# CarrotDriver.net
KiCad netlist of a schematic drawn in Altium Designer
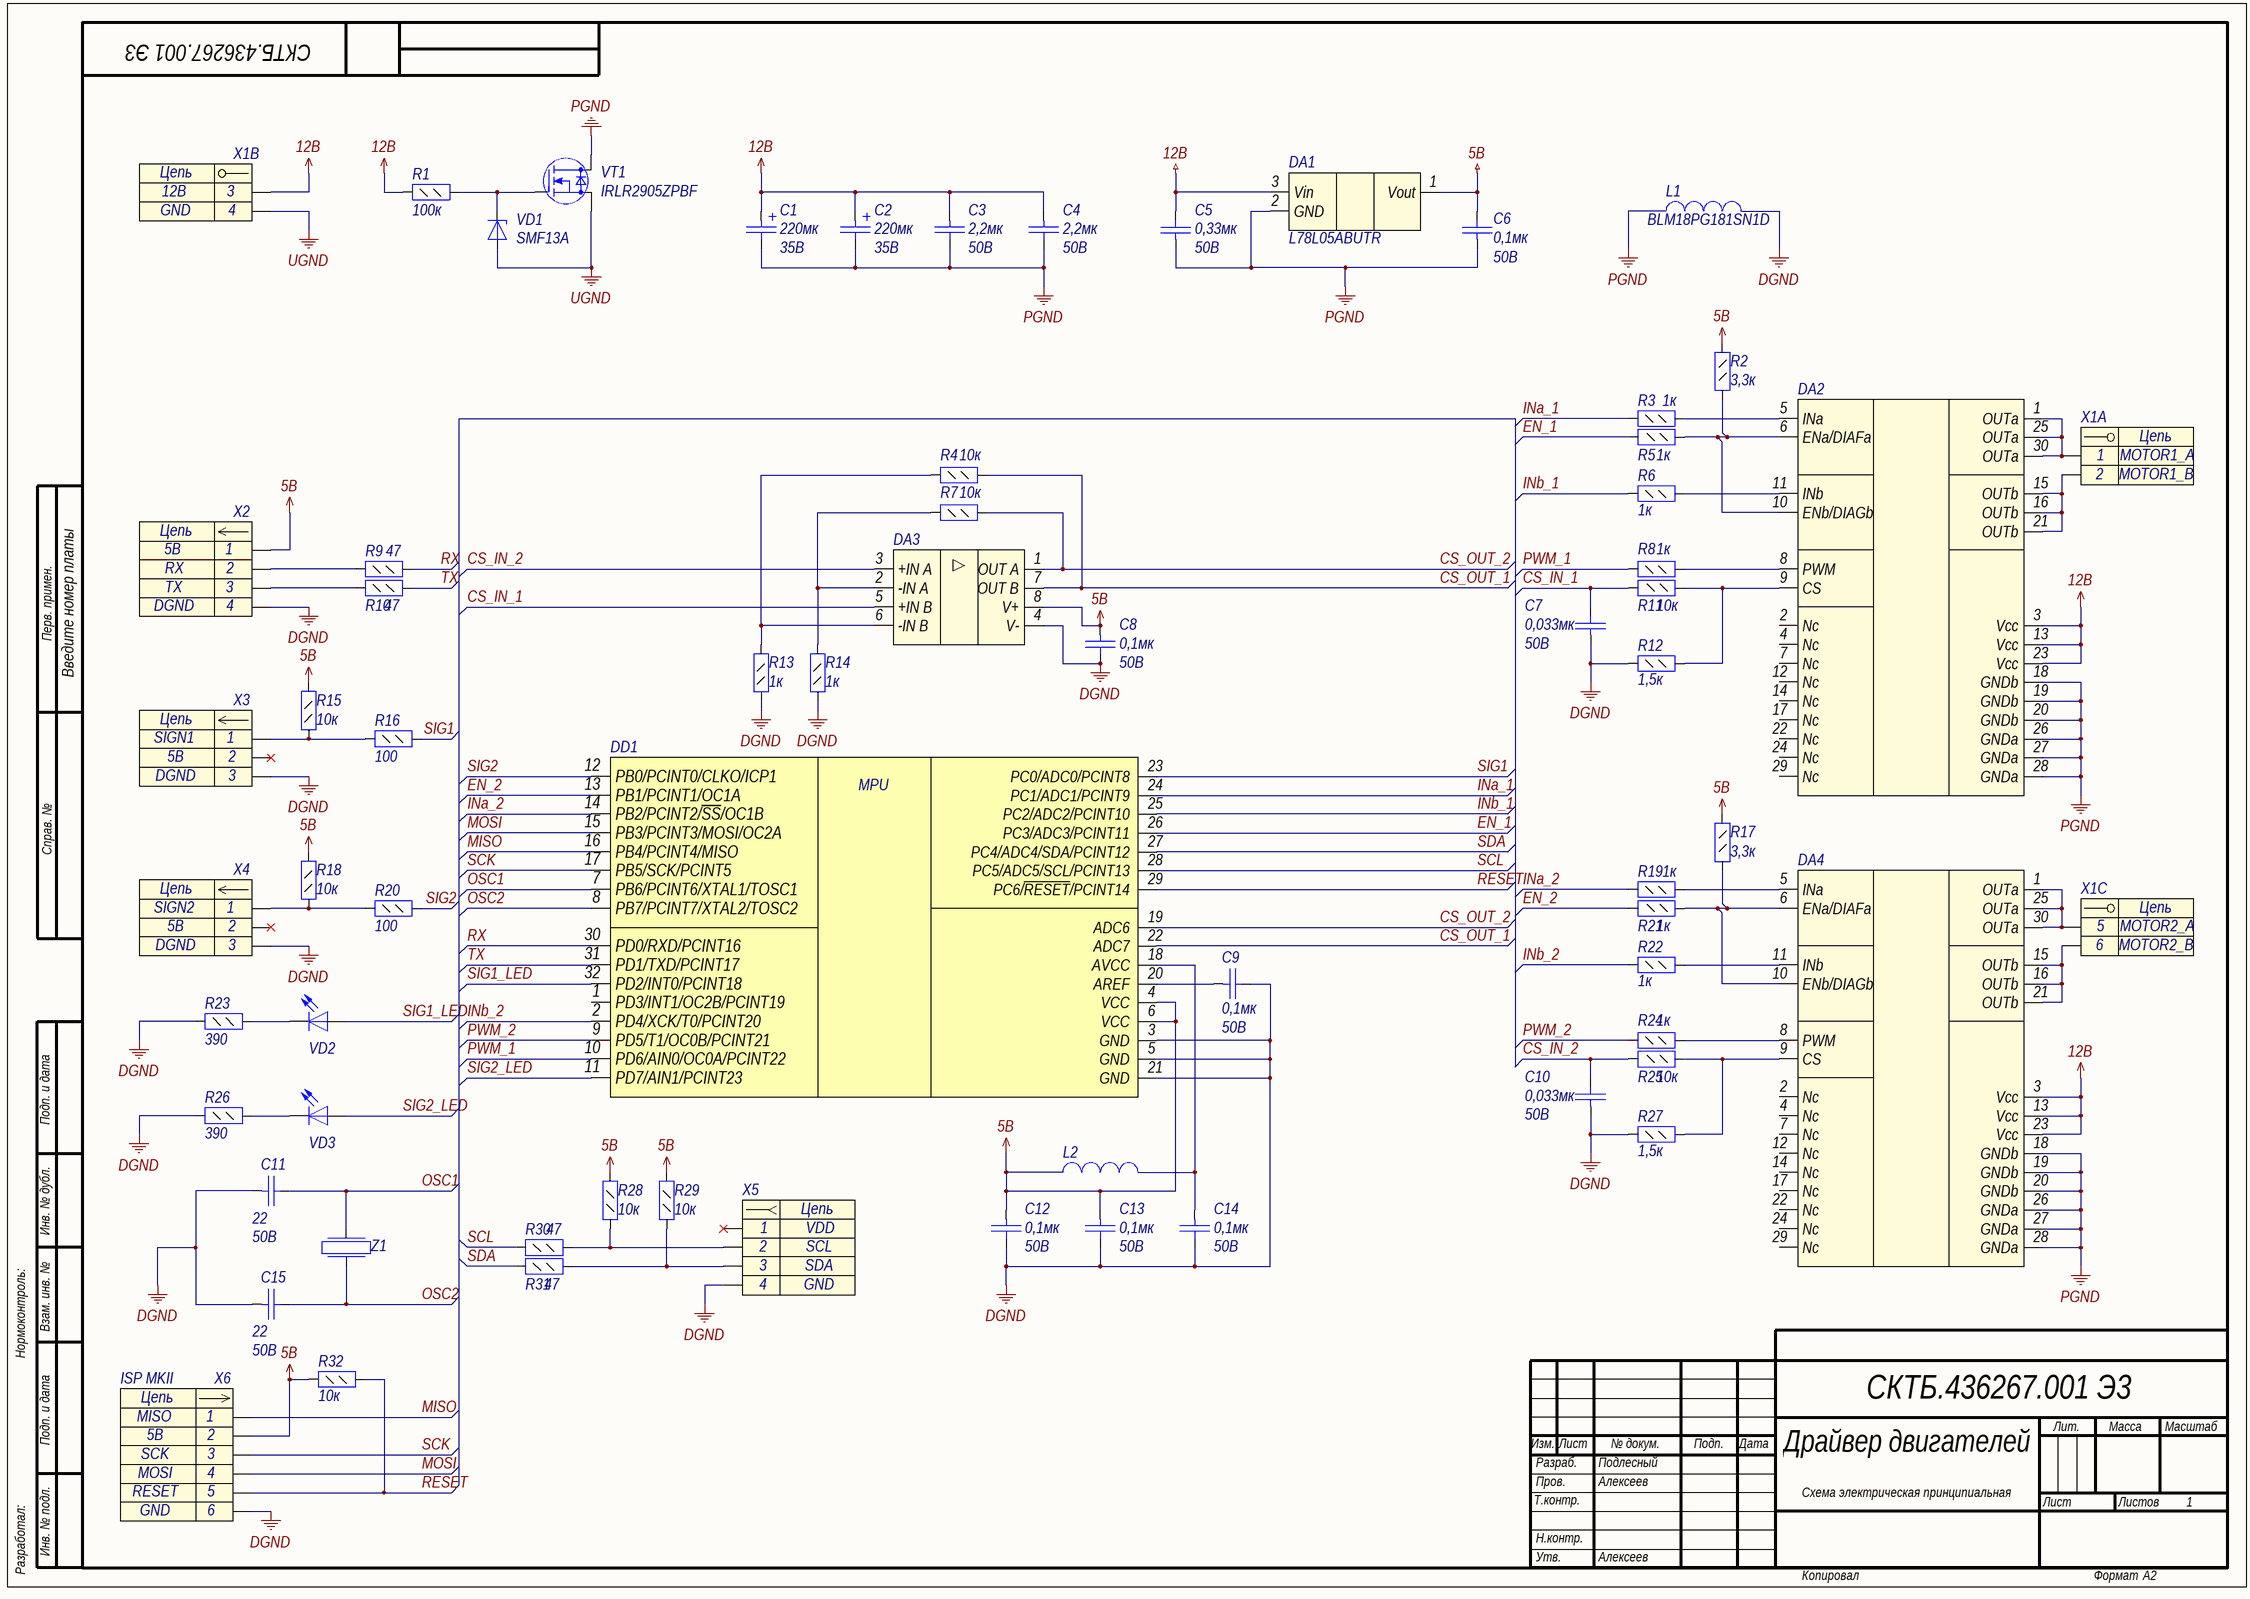
[diagram p0: CarrotDriver.SchDoc]

(export (version "E")
  (design (tool "Eeschema 10.0.6"))
  (components
    (comp (ref "C1")
      (value "220мк")
      (footprint "k50-35(8x11.5)_MIRROR")
      (description "Конденсатор полярный")
      (fields
        (field (name "VOLTAGE") "35В")
        (field (name "PART NUMBER") "TKR221M1VF11")
        (field (name "Comment") "Capacitor_pol")
      )
      (libsource (lib "MOP44") (part "Capacitor_pol"))
    )
    (comp (ref "C2")
      (value "220мк")
      (footprint "k50-35(8x11.5)_MIRROR")
      (description "Конденсатор полярный")
      (fields
        (field (name "VOLTAGE") "35В")
        (field (name "PART NUMBER") "TKR221M1VF11")
        (field (name "Comment") "Capacitor_pol")
      )
      (libsource (lib "MOP44") (part "Capacitor_pol"))
    )
    (comp (ref "C3")
      (value "2,2мк")
      (footprint "C1206")
      (description "Конденсатор")
      (fields
        (field (name "VOLTAGE") "50В")
        (field (name "PART NUMBER") "GRM31CR71H225KA88**L")
        (field (name "Comment") "Capacitor")
      )
      (libsource (lib "MOP44") (part "Capacitor"))
    )
    (comp (ref "C4")
      (value "2,2мк")
      (footprint "C1206")
      (description "Конденсатор")
      (fields
        (field (name "VOLTAGE") "50В")
        (field (name "PART NUMBER") "GRM31CR71H225KA88**L")
        (field (name "Comment") "Capacitor")
      )
      (libsource (lib "MOP44") (part "Capacitor"))
    )
    (comp (ref "C5")
      (value "0,33мк")
      (footprint "C1206")
      (description "Конденсатор")
      (fields
        (field (name "VOLTAGE") "50В")
        (field (name "PART NUMBER") "GRM319R71H334K")
        (field (name "Comment") "Capacitor")
      )
      (libsource (lib "MOP44") (part "Capacitor"))
    )
    (comp (ref "C6")
      (value "0,1мк")
      (footprint "C0805")
      (description "Конденсатор")
      (fields
        (field (name "VOLTAGE") "50В")
        (field (name "PART NUMBER") "GRM21BR71H104KA01L ")
        (field (name "Comment") "Capacitor")
      )
      (libsource (lib "MOP44") (part "Capacitor"))
    )
    (comp (ref "C7")
      (value "0,033мк")
      (footprint "C1206")
      (description "Конденсатор")
      (fields
        (field (name "VOLTAGE") "50В")
        (field (name "PART NUMBER") "GRM3195C1H333J")
        (field (name "Comment") "Capacitor")
      )
      (libsource (lib "MOP44") (part "Capacitor"))
    )
    (comp (ref "C8")
      (value "0,1мк")
      (footprint "C0805")
      (description "Конденсатор")
      (fields
        (field (name "VOLTAGE") "50В")
        (field (name "PART NUMBER") "GRM216R71H221K")
        (field (name "Comment") "Capacitor")
      )
      (libsource (lib "MOP44") (part "Capacitor"))
    )
    (comp (ref "C9")
      (value "0,1мк")
      (footprint "C0805")
      (description "Конденсатор")
      (fields
        (field (name "VOLTAGE") "50В")
        (field (name "PART NUMBER") "GRM216R71H221K")
        (field (name "Comment") "Capacitor")
      )
      (libsource (lib "MOP44") (part "Capacitor"))
    )
    (comp (ref "C10")
      (value "0,033мк")
      (footprint "C1206")
      (description "Конденсатор")
      (fields
        (field (name "VOLTAGE") "50В")
        (field (name "PART NUMBER") "GRM3195C1H333J")
        (field (name "Comment") "Capacitor")
      )
      (libsource (lib "MOP44") (part "Capacitor"))
    )
    (comp (ref "C11")
      (value "22")
      (footprint "C0805")
      (description "Конденсатор")
      (fields
        (field (name "VOLTAGE") "50В")
        (field (name "PART NUMBER") "GRM21A5C2E220JW01D")
        (field (name "Comment") "Capacitor")
      )
      (libsource (lib "MOP44") (part "Capacitor"))
    )
    (comp (ref "C12")
      (value "0,1мк")
      (footprint "C0805")
      (description "Конденсатор")
      (fields
        (field (name "VOLTAGE") "50В")
        (field (name "PART NUMBER") "GRM216R71H221K")
        (field (name "Comment") "Capacitor")
      )
      (libsource (lib "MOP44") (part "Capacitor"))
    )
    (comp (ref "C13")
      (value "0,1мк")
      (footprint "C0805")
      (description "Конденсатор")
      (fields
        (field (name "VOLTAGE") "50В")
        (field (name "PART NUMBER") "GRM216R71H221K")
        (field (name "Comment") "Capacitor")
      )
      (libsource (lib "MOP44") (part "Capacitor"))
    )
    (comp (ref "C14")
      (value "0,1мк")
      (footprint "C0805")
      (description "Конденсатор")
      (fields
        (field (name "VOLTAGE") "50В")
        (field (name "PART NUMBER") "GRM216R71H221K")
        (field (name "Comment") "Capacitor")
      )
      (libsource (lib "MOP44") (part "Capacitor"))
    )
    (comp (ref "C15")
      (value "22")
      (footprint "C0805")
      (description "Конденсатор")
      (fields
        (field (name "VOLTAGE") "50В")
        (field (name "PART NUMBER") "GRM21A5C2E220JW01D")
        (field (name "Comment") "Capacitor")
      )
      (libsource (lib "MOP44") (part "Capacitor"))
    )
    (comp (ref "DA1")
      (value "L78L05ABUTR")
      (footprint "SOT-89-3")
      (description "Cтабилизатор напряжения (+5В; 0.1А), 4%, (-40...+125C)")
      (fields (field (name "MANUFACTURER") "ST Microelectronics"))
      (libsource (lib "MOP44") (part "L78L05ABUTR"))
    )
    (comp (ref "DA2")
      (value "VNH2SP30-E")
      (footprint "MultiPowerSO-30")
      (description "Automotive fully integrated H-bridge motor driver")
      (libsource (lib "MOP44") (part "VNH2SP30-E"))
    )
    (comp (ref "DA3")
      (value "LMV358IDR")
      (footprint "SO8")
      (description "LOW-VOLTAGE RAIL-TO-RAIL OUTPUT OPERATIONAL AMPLIFIERS")
      (libsource (lib "MOP44") (part "LMV358IDR"))
    )
    (comp (ref "DA4")
      (value "VNH2SP30-E")
      (footprint "MultiPowerSO-30")
      (description "Automotive fully integrated H-bridge motor driver")
      (libsource (lib "MOP44") (part "VNH2SP30-E"))
    )
    (comp (ref "DD1")
      (value "ATmega328P-AU")
      (footprint "TQFP-32")
      (description "Микроконтроллер 8-Бит, picoPower, AVR, 20МГц, 32КБ Flash")
      (libsource (lib "MOP44") (part "ATmega328P-AU"))
    )
    (comp (ref "L1")
      (value "Inductor")
      (footprint "L0603")
      (description "EMI Suppression Filter")
      (fields (field (name "PART NUMBER") "BLM18PG181SN1D"))
      (libsource (lib "MOP44") (part "Inductor"))
    )
    (comp (ref "L2")
      (value "Inductor")
      (footprint "L0603")
      (description "EMI Suppression Filter")
      (fields (field (name "PART NUMBER") "BLM18PG181SN1D"))
      (libsource (lib "MOP44") (part "Inductor"))
    )
    (comp (ref "R1")
      (value "100к")
      (footprint "R0805")
      (description "Резистор")
      (fields (field (name "PART NUMBER") "RC0805FR-07100KL") (field (name "POWER") "0,125Вт"))
      (libsource (lib "MOP44") (part "Resistor_0,125Вт"))
    )
    (comp (ref "R2")
      (value "3,3к")
      (footprint "R0805")
      (description "Резистор")
      (fields (field (name "PART NUMBER") "RC0805FR-0710KL") (field (name "POWER") "0,125Вт"))
      (libsource (lib "") (part "Resistor_0,125Вт_3"))
    )
    (comp (ref "R3")
      (value "1к")
      (footprint "R0805")
      (description "Резистор")
      (fields (field (name "PART NUMBER") "RC0805FR-0710KL") (field (name "POWER") "0,125Вт"))
      (libsource (lib "MOP44") (part "Resistor_0,125Вт"))
    )
    (comp (ref "R4")
      (value "10к")
      (footprint "R0805")
      (description "Резистор")
      (fields (field (name "PART NUMBER") "RC0805FR-0710KL") (field (name "POWER") "0,125Вт"))
      (libsource (lib "MOP44") (part "Resistor_0,125Вт"))
    )
    (comp (ref "R5")
      (value "1к")
      (footprint "R0805")
      (description "Резистор")
      (fields (field (name "PART NUMBER") "RC0805FR-0710KL") (field (name "POWER") "0,125Вт"))
      (libsource (lib "") (part "Resistor_0,125Вт_1"))
    )
    (comp (ref "R6")
      (value "1к")
      (footprint "R0805")
      (description "Резистор")
      (fields (field (name "PART NUMBER") "RC0805FR-0710KL") (field (name "POWER") "0,125Вт"))
      (libsource (lib "MOP44") (part "Resistor_0,125Вт"))
    )
    (comp (ref "R7")
      (value "10к")
      (footprint "R0805")
      (description "Резистор")
      (fields (field (name "PART NUMBER") "RC0805FR-0710KL") (field (name "POWER") "0,125Вт"))
      (libsource (lib "MOP44") (part "Resistor_0,125Вт"))
    )
    (comp (ref "R8")
      (value "1к")
      (footprint "R0805")
      (description "Резистор")
      (fields (field (name "PART NUMBER") "RC0805FR-0710KL") (field (name "POWER") "0,125Вт"))
      (libsource (lib "MOP44") (part "Resistor_0,125Вт"))
    )
    (comp (ref "R9")
      (value "47")
      (footprint "R0805")
      (description "Резистор")
      (fields (field (name "PART NUMBER") "RC0805FR-0747RL") (field (name "POWER") "0,125Вт"))
      (libsource (lib "MOP44") (part "Resistor_0,125Вт"))
    )
    (comp (ref "R10")
      (value "47")
      (footprint "R0805")
      (description "Резистор")
      (fields (field (name "PART NUMBER") "RC0805FR-0747RL") (field (name "POWER") "0,125Вт"))
      (libsource (lib "MOP44") (part "Resistor_0,125Вт"))
    )
    (comp (ref "R11")
      (value "10к")
      (footprint "R0805")
      (description "Резистор")
      (fields (field (name "PART NUMBER") "RC0805FR-0710KL") (field (name "POWER") "0,125Вт"))
      (libsource (lib "") (part "Resistor_0,125Вт_1"))
    )
    (comp (ref "R12")
      (value "1,5к")
      (footprint "R0805")
      (description "Резистор")
      (fields (field (name "PART NUMBER") "RC0805FR-0710KL") (field (name "POWER") "0,125Вт"))
      (libsource (lib "MOP44") (part "Resistor_0,125Вт"))
    )
    (comp (ref "R13")
      (value "1к")
      (footprint "R0805")
      (description "Резистор")
      (fields (field (name "PART NUMBER") "RC0805FR-071KL") (field (name "POWER") "0,125Вт"))
      (libsource (lib "") (part "Resistor_0,125Вт_2"))
    )
    (comp (ref "R14")
      (value "1к")
      (footprint "R0805")
      (description "Резистор")
      (fields (field (name "PART NUMBER") "RC0805FR-071KL") (field (name "POWER") "0,125Вт"))
      (libsource (lib "") (part "Resistor_0,125Вт_2"))
    )
    (comp (ref "R15")
      (value "10к")
      (footprint "R0805")
      (description "Резистор")
      (fields (field (name "PART NUMBER") "RC0805FR-0710KL") (field (name "POWER") "0,125Вт"))
      (libsource (lib "") (part "Resistor_0,125Вт_2"))
    )
    (comp (ref "R16")
      (value "100")
      (footprint "R0805")
      (description "Резистор")
      (fields (field (name "PART NUMBER") "RC0805FR-07100RL") (field (name "POWER") "0,125Вт"))
      (libsource (lib "MOP44") (part "Resistor_0,125Вт"))
    )
    (comp (ref "R17")
      (value "3,3к")
      (footprint "R0805")
      (description "Резистор")
      (fields (field (name "PART NUMBER") "RC0805FR-0710KL") (field (name "POWER") "0,125Вт"))
      (libsource (lib "") (part "Resistor_0,125Вт_3"))
    )
    (comp (ref "R18")
      (value "10к")
      (footprint "R0805")
      (description "Резистор")
      (fields (field (name "PART NUMBER") "RC0805FR-0710KL") (field (name "POWER") "0,125Вт"))
      (libsource (lib "") (part "Resistor_0,125Вт_2"))
    )
    (comp (ref "R19")
      (value "1к")
      (footprint "R0805")
      (description "Резистор")
      (fields (field (name "PART NUMBER") "RC0805FR-0710KL") (field (name "POWER") "0,125Вт"))
      (libsource (lib "MOP44") (part "Resistor_0,125Вт"))
    )
    (comp (ref "R20")
      (value "100")
      (footprint "R0805")
      (description "Резистор")
      (fields (field (name "PART NUMBER") "RC0805FR-07100RL") (field (name "POWER") "0,125Вт"))
      (libsource (lib "MOP44") (part "Resistor_0,125Вт"))
    )
    (comp (ref "R21")
      (value "1к")
      (footprint "R0805")
      (description "Резистор")
      (fields (field (name "PART NUMBER") "RC0805FR-0710KL") (field (name "POWER") "0,125Вт"))
      (libsource (lib "") (part "Resistor_0,125Вт_1"))
    )
    (comp (ref "R22")
      (value "1к")
      (footprint "R0805")
      (description "Резистор")
      (fields (field (name "PART NUMBER") "RC0805FR-0710KL") (field (name "POWER") "0,125Вт"))
      (libsource (lib "MOP44") (part "Resistor_0,125Вт"))
    )
    (comp (ref "R23")
      (value "390")
      (footprint "R0805")
      (description "Резистор")
      (fields (field (name "PART NUMBER") "RC0805FR-07390RL") (field (name "POWER") "0,125Вт"))
      (libsource (lib "MOP44") (part "Resistor_0,125Вт"))
    )
    (comp (ref "R24")
      (value "1к")
      (footprint "R0805")
      (description "Резистор")
      (fields (field (name "PART NUMBER") "RC0805FR-0710KL") (field (name "POWER") "0,125Вт"))
      (libsource (lib "MOP44") (part "Resistor_0,125Вт"))
    )
    (comp (ref "R25")
      (value "10к")
      (footprint "R0805")
      (description "Резистор")
      (fields (field (name "PART NUMBER") "RC0805FR-0710KL") (field (name "POWER") "0,125Вт"))
      (libsource (lib "") (part "Resistor_0,125Вт_1"))
    )
    (comp (ref "R26")
      (value "390")
      (footprint "R0805")
      (description "Резистор")
      (fields (field (name "PART NUMBER") "RC0805FR-07390RL") (field (name "POWER") "0,125Вт"))
      (libsource (lib "MOP44") (part "Resistor_0,125Вт"))
    )
    (comp (ref "R27")
      (value "1,5к")
      (footprint "R0805")
      (description "Резистор")
      (fields (field (name "PART NUMBER") "RC0805FR-0710KL") (field (name "POWER") "0,125Вт"))
      (libsource (lib "MOP44") (part "Resistor_0,125Вт"))
    )
    (comp (ref "R28")
      (value "10к")
      (footprint "R0805")
      (description "Резистор")
      (fields (field (name "PART NUMBER") "RC0805FR-0710KL") (field (name "POWER") "0,125Вт"))
      (libsource (lib "MOP44") (part "Resistor_0,125Вт"))
    )
    (comp (ref "R29")
      (value "10к")
      (footprint "R0805")
      (description "Резистор")
      (fields (field (name "PART NUMBER") "RC0805FR-0710KL") (field (name "POWER") "0,125Вт"))
      (libsource (lib "MOP44") (part "Resistor_0,125Вт"))
    )
    (comp (ref "R30")
      (value "47")
      (footprint "R0805")
      (description "Резистор")
      (fields (field (name "PART NUMBER") "RC0805FR-0747RL") (field (name "POWER") "0,125Вт"))
      (libsource (lib "MOP44") (part "Resistor_0,125Вт"))
    )
    (comp (ref "R31")
      (value "47")
      (footprint "R0805")
      (description "Резистор")
      (fields (field (name "PART NUMBER") "RC0805FR-0747RL") (field (name "POWER") "0,125Вт"))
      (libsource (lib "MOP44") (part "Resistor_0,125Вт"))
    )
    (comp (ref "R32")
      (value "10к")
      (footprint "R0805")
      (description "Резистор")
      (fields (field (name "PART NUMBER") "RC0805FR-0710KL") (field (name "POWER") "0,125Вт"))
      (libsource (lib "MOP44") (part "Resistor_0,125Вт"))
    )
    (comp (ref "VD1")
      (value "DiodeZener")
      (footprint "SOD-123")
      (description "Cтабилитрон (лавинный выпрямительный диод) односторонний")
      (fields (field (name "PART NUMBER") "SMF13A"))
      (libsource (lib "MOP44") (part "DiodeZener"))
    )
    (comp (ref "VD2")
      (value "LED")
      (footprint "L_0805")
      (description "Светодиод")
      (fields (field (name "PART NUMBER") "KP-2012EC"))
      (libsource (lib "MOP44") (part "LED"))
    )
    (comp (ref "VD3")
      (value "LED")
      (footprint "L_0805")
      (description "Светодиод")
      (fields (field (name "PART NUMBER") "KP-2012EC"))
      (libsource (lib "MOP44") (part "LED"))
    )
    (comp (ref "VT1")
      (value "N-MOSFET")
      (footprint "DPAK")
      (fields
        (field (name "PART NUMBER") "IRLR2905ZPBF")
        (field (name "MANUFACTURER") "International Rectifier")
      )
      (libsource (lib "MOP44") (part "N-MOSFET"))
    )
    (comp (ref "X1")
      (value "~")
      (footprint "TERMINAL-6WAY-5MM")
      (description "POWER")
      (libsource (lib "") (part "Header_6_motor_1"))
    )
    (comp (ref "X2")
      (value "Header_4_plg")
      (footprint "PLS-4")
      (description "Разъем - 4 конт. вилка")
      (fields (field (name "PART NUMBER") "DS1021-1*4SF112-B"))
      (libsource (lib "MOP44") (part "Header_4_plg"))
    )
    (comp (ref "X3")
      (value "Header_3_plg")
      (footprint "PLS-3")
      (description "Разъем - 3 конт. вилка")
      (fields (field (name "PART NUMBER") "DS1021-1*3SF112-B"))
      (libsource (lib "MOP44") (part "Header_3_plg"))
    )
    (comp (ref "X4")
      (value "Header_3_plg")
      (footprint "PLS-3")
      (description "Разъем - 3 конт. вилка")
      (fields (field (name "PART NUMBER") "DS1021-1*3SF112-B"))
      (libsource (lib "MOP44") (part "Header_3_plg"))
    )
    (comp (ref "X5")
      (value "Header_4_sct")
      (footprint "RJ11_4P4C_V")
      (description "Разъем - 4 конт. розетка")
      (libsource (lib "MOP44") (part "Header_4_sct"))
    )
    (comp (ref "X6")
      (value "ISP MKII")
      (footprint "PLS2-6")
      (description "Разъем - 6 конт. вилка")
      (libsource (lib "MOP44") (part "ISP MKII"))
    )
    (comp (ref "Z1")
      (value "Crystal")
      (footprint "HC-49S")
      (description "Кварцевый резонатор")
      (fields (field (name "PART NUMBER") "16.000MHzHC-49US"))
      (libsource (lib "MOP44") (part "Crystal"))
    )
  )
  (nets
    (net (code "1") (name "/CS_IN_1") (class "Default")
      (node (ref "C7") (pin "2") (pinfunction "2_2") (pintype "passive"))
      (node (ref "DA3") (pin "5") (pinfunction "+IN_B_5") (pintype "passive"))
      (node (ref "R11") (pin "2") (pinfunction "2_2") (pintype "passive"))
    )
    (net (code "2") (name "/CS_IN_2") (class "Default")
      (node (ref "C10") (pin "2") (pinfunction "2_2") (pintype "passive"))
      (node (ref "DA3") (pin "3") (pinfunction "+IN_A_3") (pintype "passive"))
      (node (ref "R25") (pin "2") (pinfunction "2_2") (pintype "passive"))
    )
    (net (code "3") (name "/CS_OUT_1") (class "Default")
      (node (ref "DA3") (pin "7") (pinfunction "OUT_B_7") (pintype "passive"))
      (node (ref "DD1") (pin "22") (pinfunction "ADC7_22") (pintype "passive"))
      (node (ref "R4") (pin "2") (pinfunction "2_2") (pintype "passive"))
    )
    (net (code "4") (name "/CS_OUT_2") (class "Default")
      (node (ref "DA3") (pin "1") (pinfunction "OUT_A_1") (pintype "passive"))
      (node (ref "DD1") (pin "19") (pinfunction "ADC6_19") (pintype "passive"))
      (node (ref "R7") (pin "2") (pinfunction "2_2") (pintype "passive"))
    )
    (net (code "5") (name "/EN_1") (class "Default")
      (node (ref "DD1") (pin "26") (pinfunction "PC3/ADC3/PCINT11_26") (pintype "passive"))
      (node (ref "R5") (pin "2") (pinfunction "2_2") (pintype "passive"))
    )
    (net (code "6") (name "/EN_2") (class "Default")
      (node (ref "DD1") (pin "13") (pinfunction "PB1/PCINT1/OC1A_13") (pintype "passive"))
      (node (ref "R21") (pin "2") (pinfunction "2_2") (pintype "passive"))
    )
    (net (code "7") (name "/INa_1") (class "Default")
      (node (ref "DD1") (pin "24") (pinfunction "PC1/ADC1/PCINT9_24") (pintype "passive"))
      (node (ref "R3") (pin "1") (pinfunction "1_1") (pintype "passive"))
    )
    (net (code "8") (name "/INa_2") (class "Default")
      (node (ref "DD1") (pin "14") (pinfunction "PB2/PCINT2/~{SS}/OC1B_14") (pintype "passive"))
      (node (ref "R19") (pin "1") (pinfunction "1_1") (pintype "passive"))
    )
    (net (code "9") (name "/INb_1") (class "Default")
      (node (ref "DD1") (pin "25") (pinfunction "PC2/ADC2/PCINT10_25") (pintype "passive"))
      (node (ref "R6") (pin "1") (pinfunction "1_1") (pintype "passive"))
    )
    (net (code "10") (name "/INb_2") (class "Default")
      (node (ref "DD1") (pin "2") (pinfunction "PD4/XCK/T0/PCINT20_2") (pintype "passive"))
      (node (ref "R22") (pin "1") (pinfunction "1_1") (pintype "passive"))
    )
    (net (code "11") (name "/MISO") (class "Default")
      (node (ref "DD1") (pin "16") (pinfunction "PB4/PCINT4/MISO_16") (pintype "passive"))
      (node (ref "X6") (pin "1") (pinfunction "1_1") (pintype "passive"))
    )
    (net (code "12") (name "/MOSI") (class "Default")
      (node (ref "DD1") (pin "15") (pinfunction "PB3/PCINT3/MOSI/OC2A_15") (pintype "passive"))
      (node (ref "X6") (pin "4") (pinfunction "4_4") (pintype "passive"))
    )
    (net (code "13") (name "/OSC1") (class "Default")
      (node (ref "C11") (pin "2") (pinfunction "2_2") (pintype "passive"))
      (node (ref "DD1") (pin "7") (pinfunction "PB6/PCINT6/XTAL1/TOSC1_7") (pintype "passive"))
      (node (ref "Z1") (pin "2") (pinfunction "2_2") (pintype "passive"))
    )
    (net (code "14") (name "/OSC2") (class "Default")
      (node (ref "C15") (pin "2") (pinfunction "2_2") (pintype "passive"))
      (node (ref "DD1") (pin "8") (pinfunction "PB7/PCINT7/XTAL2/TOSC2_8") (pintype "passive"))
      (node (ref "Z1") (pin "1") (pinfunction "1_1") (pintype "passive"))
    )
    (net (code "15") (name "/PWM_1") (class "Default")
      (node (ref "DD1") (pin "10") (pinfunction "PD6/AIN0/OC0A/PCINT22_10") (pintype "passive"))
      (node (ref "R8") (pin "1") (pinfunction "1_1") (pintype "passive"))
    )
    (net (code "16") (name "/PWM_2") (class "Default")
      (node (ref "DD1") (pin "9") (pinfunction "PD5/T1/OC0B/PCINT21_9") (pintype "passive"))
      (node (ref "R24") (pin "1") (pinfunction "1_1") (pintype "passive"))
    )
    (net (code "17") (name "/RESET") (class "Default")
      (node (ref "DD1") (pin "29") (pinfunction "PC6/~{RESET}/PCINT14_29") (pintype "passive"))
      (node (ref "R32") (pin "2") (pinfunction "2_2") (pintype "passive"))
      (node (ref "X6") (pin "5") (pinfunction "5_5") (pintype "passive"))
    )
    (net (code "18") (name "/RX") (class "Default")
      (node (ref "DD1") (pin "30") (pinfunction "PD0/RXD/PCINT16_30") (pintype "passive"))
      (node (ref "R9") (pin "2") (pinfunction "2_2") (pintype "passive"))
    )
    (net (code "19") (name "/SCK") (class "Default")
      (node (ref "DD1") (pin "17") (pinfunction "PB5/SCK/PCINT5_17") (pintype "passive"))
      (node (ref "X6") (pin "3") (pinfunction "3_3") (pintype "passive"))
    )
    (net (code "20") (name "/SCL") (class "Default")
      (node (ref "DD1") (pin "28") (pinfunction "PC5/ADC5/SCL/PCINT13_28") (pintype "passive"))
      (node (ref "R30") (pin "1") (pinfunction "1_1") (pintype "passive"))
    )
    (net (code "21") (name "/SDA") (class "Default")
      (node (ref "DD1") (pin "27") (pinfunction "PC4/ADC4/SDA/PCINT12_27") (pintype "passive"))
      (node (ref "R31") (pin "1") (pinfunction "1_1") (pintype "passive"))
    )
    (net (code "22") (name "/SIG1") (class "Default")
      (node (ref "DD1") (pin "23") (pinfunction "PC0/ADC0/PCINT8_23") (pintype "passive"))
      (node (ref "R16") (pin "2") (pinfunction "2_2") (pintype "passive"))
    )
    (net (code "23") (name "/SIG1_LED") (class "Default")
      (node (ref "DD1") (pin "32") (pinfunction "PD2/INT0/PCINT18_32") (pintype "passive"))
      (node (ref "VD2") (pin "2") (pinfunction "A_2") (pintype "passive"))
    )
    (net (code "24") (name "/SIG2") (class "Default")
      (node (ref "DD1") (pin "12") (pinfunction "PB0/PCINT0/CLKO/ICP1_12") (pintype "passive"))
      (node (ref "R20") (pin "2") (pinfunction "2_2") (pintype "passive"))
    )
    (net (code "25") (name "/SIG2_LED") (class "Default")
      (node (ref "DD1") (pin "11") (pinfunction "PD7/AIN1/PCINT23_11") (pintype "passive"))
      (node (ref "VD3") (pin "2") (pinfunction "A_2") (pintype "passive"))
    )
    (net (code "26") (name "/TX") (class "Default")
      (node (ref "DD1") (pin "31") (pinfunction "PD1/TXD/PCINT17_31") (pintype "passive"))
      (node (ref "R10") (pin "2") (pinfunction "2_2") (pintype "passive"))
    )
    (net (code "27") (name "5B") (class "Default")
      (node (ref "C12") (pin "1") (pinfunction "1_1") (pintype "passive"))
      (node (ref "C13") (pin "1") (pinfunction "1_1") (pintype "passive"))
      (node (ref "C6") (pin "2") (pinfunction "2_2") (pintype "passive"))
      (node (ref "C8") (pin "1") (pinfunction "1_1") (pintype "passive"))
      (node (ref "DA1") (pin "1") (pinfunction "Vout_1") (pintype "power_in"))
      (node (ref "DA3") (pin "8") (pinfunction "V+_8") (pintype "passive"))
      (node (ref "DD1") (pin "4") (pinfunction "VCC_4") (pintype "passive"))
      (node (ref "DD1") (pin "6") (pinfunction "VCC_6") (pintype "passive"))
      (node (ref "L2") (pin "1") (pinfunction "1_1") (pintype "passive"))
      (node (ref "R15") (pin "2") (pinfunction "2_2") (pintype "passive"))
      (node (ref "R17") (pin "1") (pinfunction "1_1") (pintype "passive"))
      (node (ref "R18") (pin "2") (pinfunction "2_2") (pintype "passive"))
      (node (ref "R2") (pin "1") (pinfunction "1_1") (pintype "passive"))
      (node (ref "R28") (pin "2") (pinfunction "2_2") (pintype "passive"))
      (node (ref "R29") (pin "2") (pinfunction "2_2") (pintype "passive"))
      (node (ref "R32") (pin "1") (pinfunction "1_1") (pintype "passive"))
      (node (ref "X2") (pin "1") (pinfunction "1_1") (pintype "passive"))
      (node (ref "X6") (pin "2") (pinfunction "2_2") (pintype "passive"))
    )
    (net (code "28") (name "12B") (class "Default")
      (node (ref "C1") (pin "1") (pinfunction "1_1") (pintype "passive"))
      (node (ref "C2") (pin "1") (pinfunction "1_1") (pintype "passive"))
      (node (ref "C3") (pin "1") (pinfunction "1_1") (pintype "passive"))
      (node (ref "C4") (pin "1") (pinfunction "1_1") (pintype "passive"))
      (node (ref "C5") (pin "2") (pinfunction "2_2") (pintype "passive"))
      (node (ref "DA1") (pin "3") (pinfunction "Vin_3") (pintype "power_in"))
      (node (ref "DA2") (pin "13") (pinfunction "Vcc_13") (pintype "passive"))
      (node (ref "DA2") (pin "23") (pinfunction "Vcc_23") (pintype "passive"))
      (node (ref "DA2") (pin "3") (pinfunction "Vcc_3") (pintype "passive"))
      (node (ref "DA4") (pin "13") (pinfunction "Vcc_13") (pintype "passive"))
      (node (ref "DA4") (pin "23") (pinfunction "Vcc_23") (pintype "passive"))
      (node (ref "DA4") (pin "3") (pinfunction "Vcc_3") (pintype "passive"))
      (node (ref "R1") (pin "1") (pinfunction "1_1") (pintype "passive"))
      (node (ref "X1") (pin "3") (pinfunction "3_3") (pintype "passive"))
    )
    (net (code "29") (name "DGND") (class "Default")
      (node (ref "C10") (pin "1") (pinfunction "1_1") (pintype "passive"))
      (node (ref "C11") (pin "1") (pinfunction "1_1") (pintype "passive"))
      (node (ref "C12") (pin "2") (pinfunction "2_2") (pintype "passive"))
      (node (ref "C13") (pin "2") (pinfunction "2_2") (pintype "passive"))
      (node (ref "C14") (pin "2") (pinfunction "2_2") (pintype "passive"))
      (node (ref "C15") (pin "1") (pinfunction "1_1") (pintype "passive"))
      (node (ref "C7") (pin "1") (pinfunction "1_1") (pintype "passive"))
      (node (ref "C8") (pin "2") (pinfunction "2_2") (pintype "passive"))
      (node (ref "C9") (pin "2") (pinfunction "2_2") (pintype "passive"))
      (node (ref "DA3") (pin "4") (pinfunction "V-_4") (pintype "passive"))
      (node (ref "DD1") (pin "21") (pinfunction "GND_21") (pintype "passive"))
      (node (ref "DD1") (pin "3") (pinfunction "GND_3") (pintype "passive"))
      (node (ref "DD1") (pin "5") (pinfunction "GND_5") (pintype "passive"))
      (node (ref "L1") (pin "2") (pinfunction "2_2") (pintype "passive"))
      (node (ref "R12") (pin "1") (pinfunction "1_1") (pintype "passive"))
      (node (ref "R13") (pin "1") (pinfunction "1_1") (pintype "passive"))
      (node (ref "R14") (pin "1") (pinfunction "1_1") (pintype "passive"))
      (node (ref "R23") (pin "1") (pinfunction "1_1") (pintype "passive"))
      (node (ref "R26") (pin "1") (pinfunction "1_1") (pintype "passive"))
      (node (ref "R27") (pin "1") (pinfunction "1_1") (pintype "passive"))
      (node (ref "X2") (pin "4") (pinfunction "4_4") (pintype "passive"))
      (node (ref "X3") (pin "3") (pinfunction "3_3") (pintype "passive"))
      (node (ref "X4") (pin "3") (pinfunction "3_3") (pintype "passive"))
      (node (ref "X5") (pin "4") (pinfunction "4_4") (pintype "passive"))
      (node (ref "X6") (pin "6") (pinfunction "6_6") (pintype "passive"))
    )
    (net (code "30") (name "Net-(DA2-CS)") (class "Default")
      (node (ref "DA2") (pin "9") (pinfunction "CS_9") (pintype "passive"))
      (node (ref "R11") (pin "1") (pinfunction "1_1") (pintype "passive"))
      (node (ref "R12") (pin "2") (pinfunction "2_2") (pintype "passive"))
    )
    (net (code "31") (name "Net-(DA2-ENa{slash}DIAFa)") (class "Default")
      (node (ref "DA2") (pin "10") (pinfunction "ENb/DIAGb_10") (pintype "passive"))
      (node (ref "DA2") (pin "6") (pinfunction "ENa/DIAFa_6") (pintype "passive"))
      (node (ref "R2") (pin "2") (pinfunction "2_2") (pintype "passive"))
      (node (ref "R5") (pin "1") (pinfunction "1_1") (pintype "passive"))
    )
    (net (code "32") (name "Net-(DA2-INa)") (class "Default")
      (node (ref "DA2") (pin "5") (pinfunction "INa_5") (pintype "passive"))
      (node (ref "R3") (pin "2") (pinfunction "2_2") (pintype "passive"))
    )
    (net (code "33") (name "Net-(DA2-INb)") (class "Default")
      (node (ref "DA2") (pin "11") (pinfunction "INb_11") (pintype "passive"))
      (node (ref "R6") (pin "2") (pinfunction "2_2") (pintype "passive"))
    )
    (net (code "34") (name "Net-(DA2-OUTa-Pad1)") (class "Default")
      (node (ref "DA2") (pin "1") (pinfunction "OUTa_1") (pintype "passive"))
      (node (ref "DA2") (pin "25") (pinfunction "OUTa_25") (pintype "passive"))
      (node (ref "DA2") (pin "30") (pinfunction "OUTa_30") (pintype "passive"))
      (node (ref "X1") (pin "1") (pinfunction "1_1") (pintype "passive"))
    )
    (net (code "35") (name "Net-(DA2-OUTb-Pad15)") (class "Default")
      (node (ref "DA2") (pin "15") (pinfunction "OUTb_15") (pintype "passive"))
      (node (ref "DA2") (pin "16") (pinfunction "OUTb_16") (pintype "passive"))
      (node (ref "DA2") (pin "21") (pinfunction "OUTb_21") (pintype "passive"))
      (node (ref "X1") (pin "2") (pinfunction "2_2") (pintype "passive"))
    )
    (net (code "36") (name "Net-(DA2-PWM)") (class "Default")
      (node (ref "DA2") (pin "8") (pinfunction "PWM_8") (pintype "passive"))
      (node (ref "R8") (pin "2") (pinfunction "2_2") (pintype "passive"))
    )
    (net (code "37") (name "Net-(DA3--IN_A)") (class "Default")
      (node (ref "DA3") (pin "2") (pinfunction "-IN_A_2") (pintype "passive"))
      (node (ref "R14") (pin "2") (pinfunction "2_2") (pintype "passive"))
      (node (ref "R7") (pin "1") (pinfunction "1_1") (pintype "passive"))
    )
    (net (code "38") (name "Net-(DA3--IN_B)") (class "Default")
      (node (ref "DA3") (pin "6") (pinfunction "-IN_B_6") (pintype "passive"))
      (node (ref "R13") (pin "2") (pinfunction "2_2") (pintype "passive"))
      (node (ref "R4") (pin "1") (pinfunction "1_1") (pintype "passive"))
    )
    (net (code "39") (name "Net-(DA4-CS)") (class "Default")
      (node (ref "DA4") (pin "9") (pinfunction "CS_9") (pintype "passive"))
      (node (ref "R25") (pin "1") (pinfunction "1_1") (pintype "passive"))
      (node (ref "R27") (pin "2") (pinfunction "2_2") (pintype "passive"))
    )
    (net (code "40") (name "Net-(DA4-ENa{slash}DIAFa)") (class "Default")
      (node (ref "DA4") (pin "10") (pinfunction "ENb/DIAGb_10") (pintype "passive"))
      (node (ref "DA4") (pin "6") (pinfunction "ENa/DIAFa_6") (pintype "passive"))
      (node (ref "R17") (pin "2") (pinfunction "2_2") (pintype "passive"))
      (node (ref "R21") (pin "1") (pinfunction "1_1") (pintype "passive"))
    )
    (net (code "41") (name "Net-(DA4-INa)") (class "Default")
      (node (ref "DA4") (pin "5") (pinfunction "INa_5") (pintype "passive"))
      (node (ref "R19") (pin "2") (pinfunction "2_2") (pintype "passive"))
    )
    (net (code "42") (name "Net-(DA4-INb)") (class "Default")
      (node (ref "DA4") (pin "11") (pinfunction "INb_11") (pintype "passive"))
      (node (ref "R22") (pin "2") (pinfunction "2_2") (pintype "passive"))
    )
    (net (code "43") (name "Net-(DA4-OUTa-Pad1)") (class "Default")
      (node (ref "DA4") (pin "1") (pinfunction "OUTa_1") (pintype "passive"))
      (node (ref "DA4") (pin "25") (pinfunction "OUTa_25") (pintype "passive"))
      (node (ref "DA4") (pin "30") (pinfunction "OUTa_30") (pintype "passive"))
      (node (ref "X1") (pin "5") (pinfunction "5_5") (pintype "passive"))
    )
    (net (code "44") (name "Net-(DA4-OUTb-Pad15)") (class "Default")
      (node (ref "DA4") (pin "15") (pinfunction "OUTb_15") (pintype "passive"))
      (node (ref "DA4") (pin "16") (pinfunction "OUTb_16") (pintype "passive"))
      (node (ref "DA4") (pin "21") (pinfunction "OUTb_21") (pintype "passive"))
      (node (ref "X1") (pin "6") (pinfunction "6_6") (pintype "passive"))
    )
    (net (code "45") (name "Net-(DA4-PWM)") (class "Default")
      (node (ref "DA4") (pin "8") (pinfunction "PWM_8") (pintype "passive"))
      (node (ref "R24") (pin "2") (pinfunction "2_2") (pintype "passive"))
    )
    (net (code "46") (name "Net-(DD1-AREF)") (class "Default")
      (node (ref "C9") (pin "1") (pinfunction "1_1") (pintype "passive"))
      (node (ref "DD1") (pin "20") (pinfunction "AREF_20") (pintype "passive"))
    )
    (net (code "47") (name "Net-(DD1-AVCC)") (class "Default")
      (node (ref "C14") (pin "1") (pinfunction "1_1") (pintype "passive"))
      (node (ref "DD1") (pin "18") (pinfunction "AVCC_18") (pintype "passive"))
      (node (ref "L2") (pin "2") (pinfunction "2_2") (pintype "passive"))
    )
    (net (code "48") (name "Net-(R9-Pad1)") (class "Default")
      (node (ref "R9") (pin "1") (pinfunction "1_1") (pintype "passive"))
      (node (ref "X2") (pin "2") (pinfunction "2_2") (pintype "passive"))
    )
    (net (code "49") (name "Net-(R10-Pad1)") (class "Default")
      (node (ref "R10") (pin "1") (pinfunction "1_1") (pintype "passive"))
      (node (ref "X2") (pin "3") (pinfunction "3_3") (pintype "passive"))
    )
    (net (code "50") (name "Net-(R15-Pad1)") (class "Default")
      (node (ref "R15") (pin "1") (pinfunction "1_1") (pintype "passive"))
      (node (ref "R16") (pin "1") (pinfunction "1_1") (pintype "passive"))
      (node (ref "X3") (pin "1") (pinfunction "1_1") (pintype "passive"))
    )
    (net (code "51") (name "Net-(R18-Pad1)") (class "Default")
      (node (ref "R18") (pin "1") (pinfunction "1_1") (pintype "passive"))
      (node (ref "R20") (pin "1") (pinfunction "1_1") (pintype "passive"))
      (node (ref "X4") (pin "1") (pinfunction "1_1") (pintype "passive"))
    )
    (net (code "52") (name "Net-(R28-Pad1)") (class "Default")
      (node (ref "R28") (pin "1") (pinfunction "1_1") (pintype "passive"))
      (node (ref "R30") (pin "2") (pinfunction "2_2") (pintype "passive"))
      (node (ref "X5") (pin "2") (pinfunction "2_2") (pintype "passive"))
    )
    (net (code "53") (name "Net-(R29-Pad1)") (class "Default")
      (node (ref "R29") (pin "1") (pinfunction "1_1") (pintype "passive"))
      (node (ref "R31") (pin "2") (pinfunction "2_2") (pintype "passive"))
      (node (ref "X5") (pin "3") (pinfunction "3_3") (pintype "passive"))
    )
    (net (code "54") (name "Net-(VD1-K)") (class "Default")
      (node (ref "R1") (pin "2") (pinfunction "2_2") (pintype "passive"))
      (node (ref "VD1") (pin "1") (pinfunction "K_1") (pintype "passive"))
      (node (ref "VT1") (pin "1") (pinfunction "G_1") (pintype "passive"))
    )
    (net (code "55") (name "Net-(VD2-K)") (class "Default")
      (node (ref "R23") (pin "2") (pinfunction "2_2") (pintype "passive"))
      (node (ref "VD2") (pin "1") (pinfunction "K_1") (pintype "passive"))
    )
    (net (code "56") (name "Net-(VD3-K)") (class "Default")
      (node (ref "R26") (pin "2") (pinfunction "2_2") (pintype "passive"))
      (node (ref "VD3") (pin "1") (pinfunction "K_1") (pintype "passive"))
    )
    (net (code "57") (name "PGND") (class "Default")
      (node (ref "C1") (pin "2") (pinfunction "2_2") (pintype "passive"))
      (node (ref "C2") (pin "2") (pinfunction "2_2") (pintype "passive"))
      (node (ref "C3") (pin "2") (pinfunction "2_2") (pintype "passive"))
      (node (ref "C4") (pin "2") (pinfunction "2_2") (pintype "passive"))
      (node (ref "C5") (pin "1") (pinfunction "1_1") (pintype "passive"))
      (node (ref "C6") (pin "1") (pinfunction "1_1") (pintype "passive"))
      (node (ref "DA1") (pin "2") (pinfunction "GND_2") (pintype "power_in"))
      (node (ref "DA2") (pin "18") (pinfunction "GNDb_18") (pintype "passive"))
      (node (ref "DA2") (pin "19") (pinfunction "GNDb_19") (pintype "passive"))
      (node (ref "DA2") (pin "20") (pinfunction "GNDb_20") (pintype "passive"))
      (node (ref "DA2") (pin "26") (pinfunction "GNDa_26") (pintype "passive"))
      (node (ref "DA2") (pin "27") (pinfunction "GNDa_27") (pintype "passive"))
      (node (ref "DA2") (pin "28") (pinfunction "GNDa_28") (pintype "passive"))
      (node (ref "DA4") (pin "18") (pinfunction "GNDb_18") (pintype "passive"))
      (node (ref "DA4") (pin "19") (pinfunction "GNDb_19") (pintype "passive"))
      (node (ref "DA4") (pin "20") (pinfunction "GNDb_20") (pintype "passive"))
      (node (ref "DA4") (pin "26") (pinfunction "GNDa_26") (pintype "passive"))
      (node (ref "DA4") (pin "27") (pinfunction "GNDa_27") (pintype "passive"))
      (node (ref "DA4") (pin "28") (pinfunction "GNDa_28") (pintype "passive"))
      (node (ref "L1") (pin "1") (pinfunction "1_1") (pintype "passive"))
      (node (ref "VT1") (pin "2") (pinfunction "D_2") (pintype "passive"))
    )
    (net (code "58") (name "UGND") (class "Default")
      (node (ref "VD1") (pin "2") (pinfunction "A_2") (pintype "passive"))
      (node (ref "VT1") (pin "3") (pinfunction "S_3") (pintype "passive"))
      (node (ref "X1") (pin "4") (pinfunction "4_4") (pintype "passive"))
    )
    (net (code "59") (name "unconnected-(DA2-Nc-Pad2)") (class "Default")
      (node (ref "DA2") (pin "2") (pinfunction "Nc_2") (pintype "passive"))
    )
    (net (code "60") (name "unconnected-(DA2-Nc-Pad4)") (class "Default")
      (node (ref "DA2") (pin "4") (pinfunction "Nc_4") (pintype "passive"))
    )
    (net (code "61") (name "unconnected-(DA2-Nc-Pad7)") (class "Default")
      (node (ref "DA2") (pin "7") (pinfunction "Nc_7") (pintype "passive"))
    )
    (net (code "62") (name "unconnected-(DA2-Nc-Pad12)") (class "Default")
      (node (ref "DA2") (pin "12") (pinfunction "Nc_12") (pintype "passive"))
    )
    (net (code "63") (name "unconnected-(DA2-Nc-Pad14)") (class "Default")
      (node (ref "DA2") (pin "14") (pinfunction "Nc_14") (pintype "passive"))
    )
    (net (code "64") (name "unconnected-(DA2-Nc-Pad17)") (class "Default")
      (node (ref "DA2") (pin "17") (pinfunction "Nc_17") (pintype "passive"))
    )
    (net (code "65") (name "unconnected-(DA2-Nc-Pad22)") (class "Default")
      (node (ref "DA2") (pin "22") (pinfunction "Nc_22") (pintype "passive"))
    )
    (net (code "66") (name "unconnected-(DA2-Nc-Pad24)") (class "Default")
      (node (ref "DA2") (pin "24") (pinfunction "Nc_24") (pintype "passive"))
    )
    (net (code "67") (name "unconnected-(DA2-Nc-Pad29)") (class "Default")
      (node (ref "DA2") (pin "29") (pinfunction "Nc_29") (pintype "passive"))
    )
    (net (code "68") (name "unconnected-(DA4-Nc-Pad2)") (class "Default")
      (node (ref "DA4") (pin "2") (pinfunction "Nc_2") (pintype "passive"))
    )
    (net (code "69") (name "unconnected-(DA4-Nc-Pad4)") (class "Default")
      (node (ref "DA4") (pin "4") (pinfunction "Nc_4") (pintype "passive"))
    )
    (net (code "70") (name "unconnected-(DA4-Nc-Pad7)") (class "Default")
      (node (ref "DA4") (pin "7") (pinfunction "Nc_7") (pintype "passive"))
    )
    (net (code "71") (name "unconnected-(DA4-Nc-Pad12)") (class "Default")
      (node (ref "DA4") (pin "12") (pinfunction "Nc_12") (pintype "passive"))
    )
    (net (code "72") (name "unconnected-(DA4-Nc-Pad14)") (class "Default")
      (node (ref "DA4") (pin "14") (pinfunction "Nc_14") (pintype "passive"))
    )
    (net (code "73") (name "unconnected-(DA4-Nc-Pad17)") (class "Default")
      (node (ref "DA4") (pin "17") (pinfunction "Nc_17") (pintype "passive"))
    )
    (net (code "74") (name "unconnected-(DA4-Nc-Pad22)") (class "Default")
      (node (ref "DA4") (pin "22") (pinfunction "Nc_22") (pintype "passive"))
    )
    (net (code "75") (name "unconnected-(DA4-Nc-Pad24)") (class "Default")
      (node (ref "DA4") (pin "24") (pinfunction "Nc_24") (pintype "passive"))
    )
    (net (code "76") (name "unconnected-(DA4-Nc-Pad29)") (class "Default")
      (node (ref "DA4") (pin "29") (pinfunction "Nc_29") (pintype "passive"))
    )
    (net (code "77") (name "unconnected-(DD1-PD3{slash}INT1{slash}OC2B{slash}PCINT19-Pad1)") (class "Default")
      (node (ref "DD1") (pin "1") (pinfunction "PD3/INT1/OC2B/PCINT19_1") (pintype "passive"))
    )
    (net (code "78") (name "unconnected-(X3-Pad2)") (class "Default")
      (node (ref "X3") (pin "2") (pinfunction "2_2") (pintype "passive+no_connect"))
    )
    (net (code "79") (name "unconnected-(X4-Pad2)") (class "Default")
      (node (ref "X4") (pin "2") (pinfunction "2_2") (pintype "passive+no_connect"))
    )
    (net (code "80") (name "unconnected-(X5-Pad1)") (class "Default")
      (node (ref "X5") (pin "1") (pinfunction "1_1") (pintype "passive+no_connect"))
    )
  )
)
